# H-Bridge.net
KiCad netlist of a schematic drawn in Altium Designer
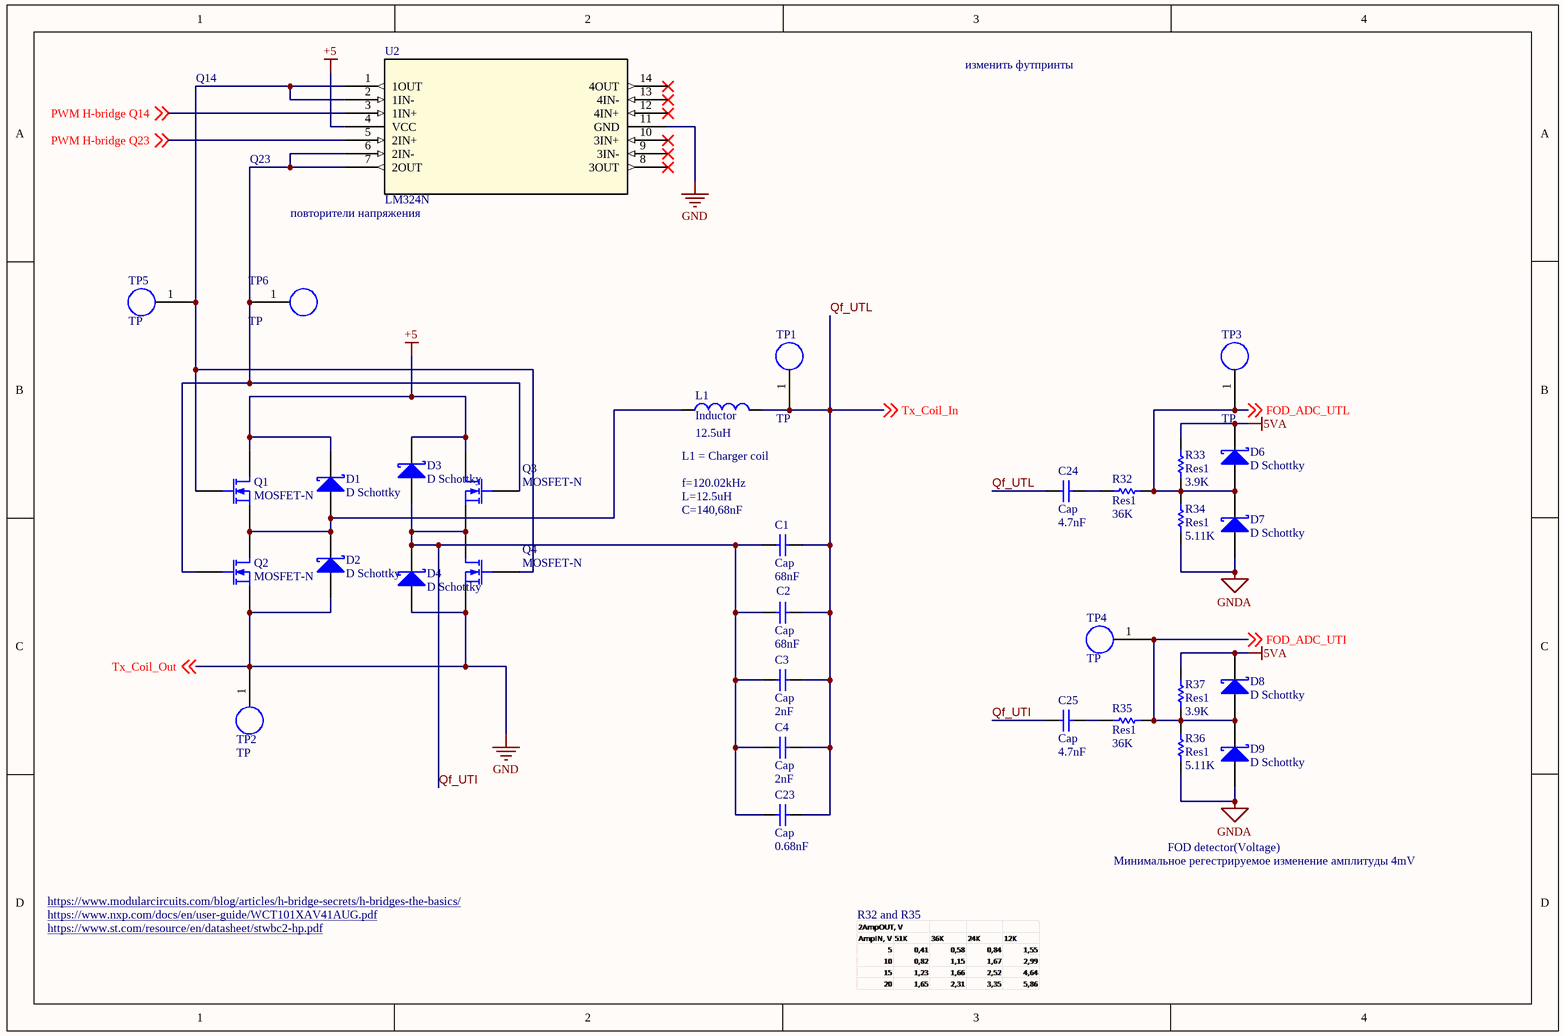
[diagram p0: H-Bridge.SchDoc]

(export (version "E")
  (design (tool "Eeschema 10.0.6"))
  (components
    (comp (ref "C1")
      (value "Cap")
      (footprint "CAP 0603_1608")
      (description "Capacitor")
      (fields (field (name "ALTIUM_VALUE") "68nF") (field (name "PUBLISHER") "Altium Limited"))
      (libsource (lib "Miscellaneous Devices") (part "Cap"))
    )
    (comp (ref "C2")
      (value "Cap")
      (footprint "CAP 0603_1608")
      (description "Capacitor")
      (fields (field (name "ALTIUM_VALUE") "68nF") (field (name "PUBLISHER") "Altium Limited"))
      (libsource (lib "Miscellaneous Devices") (part "Cap"))
    )
    (comp (ref "C3")
      (value "Cap")
      (footprint "CAP 0603_1608")
      (description "Capacitor")
      (fields (field (name "ALTIUM_VALUE") "2nF") (field (name "PUBLISHER") "Altium Limited"))
      (libsource (lib "Miscellaneous Devices") (part "Cap"))
    )
    (comp (ref "C4")
      (value "Cap")
      (footprint "CAP 0603_1608")
      (description "Capacitor")
      (fields (field (name "ALTIUM_VALUE") "2nF") (field (name "PUBLISHER") "Altium Limited"))
      (libsource (lib "Miscellaneous Devices") (part "Cap"))
    )
    (comp (ref "C23")
      (value "Cap")
      (footprint "CAP 0603_1608")
      (description "Capacitor")
      (fields (field (name "ALTIUM_VALUE") "0.68nF") (field (name "PUBLISHER") "Altium Limited"))
      (libsource (lib "Miscellaneous Devices") (part "Cap"))
    )
    (comp (ref "C24")
      (value "Cap")
      (footprint "CAP 0402_1005")
      (description "Capacitor")
      (fields (field (name "ALTIUM_VALUE") "4.7nF") (field (name "PUBLISHER") "Altium Limited"))
      (libsource (lib "Miscellaneous Devices") (part "Cap"))
    )
    (comp (ref "C25")
      (value "Cap")
      (footprint "CAP 0402_1005")
      (description "Capacitor")
      (fields (field (name "ALTIUM_VALUE") "4.7nF") (field (name "PUBLISHER") "Altium Limited"))
      (libsource (lib "Miscellaneous Devices") (part "Cap"))
    )
    (comp (ref "D1")
      (value "D Schottky")
      (footprint "SOD-123")
      (description "Schottky Diode")
      (fields (field (name "PUBLISHER") "Altium Limited"))
      (libsource (lib "Miscellaneous Devices") (part "D Schottky"))
    )
    (comp (ref "D2")
      (value "D Schottky")
      (footprint "SOD-123")
      (description "Schottky Diode")
      (fields (field (name "PUBLISHER") "Altium Limited"))
      (libsource (lib "Miscellaneous Devices") (part "D Schottky"))
    )
    (comp (ref "D3")
      (value "D Schottky")
      (footprint "SOD-123")
      (description "Schottky Diode")
      (fields (field (name "PUBLISHER") "Altium Limited"))
      (libsource (lib "Miscellaneous Devices") (part "D Schottky"))
    )
    (comp (ref "D4")
      (value "D Schottky")
      (footprint "SOD-123")
      (description "Schottky Diode")
      (fields (field (name "PUBLISHER") "Altium Limited"))
      (libsource (lib "Miscellaneous Devices") (part "D Schottky"))
    )
    (comp (ref "D6")
      (value "D Schottky")
      (footprint "SOD-123")
      (description "Schottky Diode")
      (fields (field (name "PUBLISHER") "Altium Limited"))
      (libsource (lib "Miscellaneous Devices") (part "D Schottky"))
    )
    (comp (ref "D7")
      (value "D Schottky")
      (footprint "SOD-123")
      (description "Schottky Diode")
      (fields (field (name "PUBLISHER") "Altium Limited"))
      (libsource (lib "Miscellaneous Devices") (part "D Schottky"))
    )
    (comp (ref "D8")
      (value "D Schottky")
      (footprint "SOD-123")
      (description "Schottky Diode")
      (fields (field (name "PUBLISHER") "Altium Limited"))
      (libsource (lib "Miscellaneous Devices") (part "D Schottky"))
    )
    (comp (ref "D9")
      (value "D Schottky")
      (footprint "SOD-123")
      (description "Schottky Diode")
      (fields (field (name "PUBLISHER") "Altium Limited"))
      (libsource (lib "Miscellaneous Devices") (part "D Schottky"))
    )
    (comp (ref "L1")
      (value "Inductor")
      (footprint "Charger_Coil1")
      (fields (field (name "ALTIUM_VALUE") "12.5uH") (field (name "PUBLISHER") "Altium Limited"))
      (libsource (lib "Miscellaneous Devices") (part "Inductor"))
    )
    (comp (ref "Q1")
      (value "MOSFET-N")
      (footprint "DIODES SOT-23-3")
      (description "N-Channel MOSFET")
      (fields (field (name "PUBLISHER") "Altium Limited"))
      (libsource (lib "Miscellaneous Devices") (part "MOSFET-N"))
    )
    (comp (ref "Q2")
      (value "MOSFET-N")
      (footprint "DIODES SOT-23-3")
      (description "N-Channel MOSFET")
      (fields (field (name "PUBLISHER") "Altium Limited"))
      (libsource (lib "Miscellaneous Devices") (part "MOSFET-N"))
    )
    (comp (ref "Q3")
      (value "MOSFET-N")
      (footprint "DIODES SOT-23-3")
      (description "N-Channel MOSFET")
      (fields (field (name "PUBLISHER") "Altium Limited"))
      (libsource (lib "Miscellaneous Devices") (part "MOSFET-N"))
    )
    (comp (ref "Q4")
      (value "MOSFET-N")
      (footprint "DIODES SOT-23-3")
      (description "N-Channel MOSFET")
      (fields (field (name "PUBLISHER") "Altium Limited"))
      (libsource (lib "Miscellaneous Devices") (part "MOSFET-N"))
    )
    (comp (ref "R32")
      (value "Res1")
      (footprint "RES 0402_1005")
      (description "Resistor")
      (fields (field (name "ALTIUM_VALUE") "36K") (field (name "PUBLISHER") "Altium Limited"))
      (libsource (lib "Miscellaneous Devices") (part "Res1"))
    )
    (comp (ref "R33")
      (value "Res1")
      (footprint "RES 0402_1005")
      (description "Resistor")
      (fields (field (name "ALTIUM_VALUE") "3.9K") (field (name "PUBLISHER") "Altium Limited"))
      (libsource (lib "Miscellaneous Devices") (part "Res1"))
    )
    (comp (ref "R34")
      (value "Res1")
      (footprint "RES 0603_1608")
      (description "Resistor")
      (fields (field (name "ALTIUM_VALUE") "5.11K") (field (name "PUBLISHER") "Altium Limited"))
      (libsource (lib "Miscellaneous Devices") (part "Res1"))
    )
    (comp (ref "R35")
      (value "Res1")
      (footprint "RES 0402_1005")
      (description "Resistor")
      (fields (field (name "ALTIUM_VALUE") "36K") (field (name "PUBLISHER") "Altium Limited"))
      (libsource (lib "Miscellaneous Devices") (part "Res1"))
    )
    (comp (ref "R36")
      (value "Res1")
      (footprint "RES 0603_1608")
      (description "Resistor")
      (fields (field (name "ALTIUM_VALUE") "5.11K") (field (name "PUBLISHER") "Altium Limited"))
      (libsource (lib "Miscellaneous Devices") (part "Res1"))
    )
    (comp (ref "R37")
      (value "Res1")
      (footprint "RES 0402_1005")
      (description "Resistor")
      (fields (field (name "ALTIUM_VALUE") "3.9K") (field (name "PUBLISHER") "Altium Limited"))
      (libsource (lib "Miscellaneous Devices") (part "Res1"))
    )
    (comp (ref "TP1")
      (value "TP")
      (footprint "Testpoint1")
      (libsource (lib "Testpoint1") (part "Testpoint1"))
    )
    (comp (ref "TP2")
      (value "TP")
      (footprint "Testpoint1")
      (libsource (lib "Testpoint1") (part "Testpoint1"))
    )
    (comp (ref "TP3")
      (value "TP")
      (footprint "Testpoint1")
      (libsource (lib "Testpoint1") (part "Testpoint1"))
    )
    (comp (ref "TP4")
      (value "TP")
      (footprint "Testpoint1")
      (libsource (lib "Testpoint1") (part "Testpoint1"))
    )
    (comp (ref "TP5")
      (value "TP")
      (footprint "Testpoint1")
      (libsource (lib "Testpoint1") (part "Testpoint1"))
    )
    (comp (ref "TP6")
      (value "TP")
      (footprint "Testpoint1")
      (libsource (lib "Testpoint1") (part "Testpoint1"))
    )
    (comp (ref "U2")
      (value "LM324N")
      (footprint "LM324NSR")
      (description "No Description Available")
      (libsource (lib "LM324N") (part "LM324N"))
    )
  )
  (nets
    (net (code "1") (name "+5") (class "Default")
      (node (ref "D1") (pin "2") (pinfunction "K_2") (pintype "passive"))
      (node (ref "D3") (pin "2") (pinfunction "K_2") (pintype "passive"))
      (node (ref "Q1") (pin "1") (pinfunction "D_1") (pintype "passive"))
      (node (ref "Q3") (pin "1") (pinfunction "D_1") (pintype "passive"))
      (node (ref "U2") (pin "4") (pinfunction "VCC_4") (pintype "power_in"))
    )
    (net (code "2") (name "/Qf_UTI") (class "Default")
      (node (ref "C1") (pin "1") (pinfunction "1_1") (pintype "passive"))
      (node (ref "C2") (pin "1") (pinfunction "1_1") (pintype "passive"))
      (node (ref "C23") (pin "2") (pinfunction "2_2") (pintype "passive"))
      (node (ref "C25") (pin "1") (pinfunction "1_1") (pintype "passive"))
      (node (ref "C3") (pin "1") (pinfunction "1_1") (pintype "passive"))
      (node (ref "C4") (pin "1") (pinfunction "1_1") (pintype "passive"))
      (node (ref "D3") (pin "1") (pinfunction "A_1") (pintype "passive"))
      (node (ref "D4") (pin "2") (pinfunction "K_2") (pintype "passive"))
      (node (ref "Q3") (pin "3") (pinfunction "S_3") (pintype "passive"))
      (node (ref "Q4") (pin "1") (pinfunction "D_1") (pintype "passive"))
    )
    (net (code "3") (name "5VA") (class "Default")
      (node (ref "D6") (pin "2") (pinfunction "K_2") (pintype "passive"))
      (node (ref "D8") (pin "2") (pinfunction "K_2") (pintype "passive"))
      (node (ref "R33") (pin "1") (pinfunction "1_1") (pintype "passive"))
      (node (ref "R37") (pin "2") (pinfunction "2_2") (pintype "passive"))
    )
    (net (code "4") (name "FOD_ADC_UTI") (class "Default")
      (node (ref "D8") (pin "1") (pinfunction "A_1") (pintype "passive"))
      (node (ref "D9") (pin "2") (pinfunction "K_2") (pintype "passive"))
      (node (ref "R35") (pin "2") (pinfunction "2_2") (pintype "passive"))
      (node (ref "R36") (pin "2") (pinfunction "2_2") (pintype "passive"))
      (node (ref "R37") (pin "1") (pinfunction "1_1") (pintype "passive"))
      (node (ref "TP4") (pin "1") (pintype "passive"))
    )
    (net (code "5") (name "FOD_ADC_UTL") (class "Default")
      (node (ref "D6") (pin "1") (pinfunction "A_1") (pintype "passive"))
      (node (ref "D7") (pin "2") (pinfunction "K_2") (pintype "passive"))
      (node (ref "R32") (pin "1") (pinfunction "1_1") (pintype "passive"))
      (node (ref "R33") (pin "2") (pinfunction "2_2") (pintype "passive"))
      (node (ref "R34") (pin "2") (pinfunction "2_2") (pintype "passive"))
      (node (ref "TP3") (pin "1") (pintype "passive"))
    )
    (net (code "6") (name "GND") (class "Default")
      (node (ref "D2") (pin "1") (pinfunction "A_1") (pintype "passive"))
      (node (ref "D4") (pin "1") (pinfunction "A_1") (pintype "passive"))
      (node (ref "Q2") (pin "3") (pinfunction "S_3") (pintype "passive"))
      (node (ref "Q4") (pin "3") (pinfunction "S_3") (pintype "passive"))
      (node (ref "TP2") (pin "1") (pintype "passive"))
      (node (ref "U2") (pin "11") (pinfunction "GND_11") (pintype "power_in"))
    )
    (net (code "7") (name "GNDA") (class "Default")
      (node (ref "D7") (pin "1") (pinfunction "A_1") (pintype "passive"))
      (node (ref "D9") (pin "1") (pinfunction "A_1") (pintype "passive"))
      (node (ref "R34") (pin "1") (pinfunction "1_1") (pintype "passive"))
      (node (ref "R36") (pin "1") (pinfunction "1_1") (pintype "passive"))
    )
    (net (code "8") (name "Net-(C24-Pad2)") (class "Default")
      (node (ref "C24") (pin "2") (pinfunction "2_2") (pintype "passive"))
      (node (ref "R32") (pin "2") (pinfunction "2_2") (pintype "passive"))
    )
    (net (code "9") (name "Net-(C25-Pad2)") (class "Default")
      (node (ref "C25") (pin "2") (pinfunction "2_2") (pintype "passive"))
      (node (ref "R35") (pin "1") (pinfunction "1_1") (pintype "passive"))
    )
    (net (code "10") (name "Net-(D1-A)") (class "Default")
      (node (ref "D1") (pin "1") (pinfunction "A_1") (pintype "passive"))
      (node (ref "D2") (pin "2") (pinfunction "K_2") (pintype "passive"))
      (node (ref "L1") (pin "1") (pinfunction "1_1") (pintype "passive"))
      (node (ref "Q1") (pin "3") (pinfunction "S_3") (pintype "passive"))
      (node (ref "Q2") (pin "1") (pinfunction "D_1") (pintype "passive"))
    )
    (net (code "11") (name "Net-(Q1-G)") (class "Default")
      (node (ref "Q1") (pin "2") (pinfunction "G_2") (pintype "passive"))
      (node (ref "Q4") (pin "2") (pinfunction "G_2") (pintype "passive"))
      (node (ref "TP5") (pin "1") (pintype "passive"))
      (node (ref "U2") (pin "1") (pinfunction "1OUT_1") (pintype "output"))
      (node (ref "U2") (pin "2") (pinfunction "1IN-_2") (pintype "input"))
    )
    (net (code "12") (name "Net-(Q2-G)") (class "Default")
      (node (ref "Q2") (pin "2") (pinfunction "G_2") (pintype "passive"))
      (node (ref "Q3") (pin "2") (pinfunction "G_2") (pintype "passive"))
      (node (ref "TP6") (pin "1") (pintype "passive"))
      (node (ref "U2") (pin "6") (pinfunction "2IN-_6") (pintype "input"))
      (node (ref "U2") (pin "7") (pinfunction "2OUT_7") (pintype "output"))
    )
    (net (code "13") (name "PWM H-bridge Q14") (class "Default")
      (node (ref "U2") (pin "3") (pinfunction "1IN+_3") (pintype "input"))
    )
    (net (code "14") (name "PWM H-bridge Q23") (class "Default")
      (node (ref "U2") (pin "5") (pinfunction "2IN+_5") (pintype "input"))
    )
    (net (code "15") (name "Tx_Coil_In") (class "Default")
      (node (ref "C1") (pin "2") (pinfunction "2_2") (pintype "passive"))
      (node (ref "C2") (pin "2") (pinfunction "2_2") (pintype "passive"))
      (node (ref "C23") (pin "1") (pinfunction "1_1") (pintype "passive"))
      (node (ref "C24") (pin "1") (pinfunction "1_1") (pintype "passive"))
      (node (ref "C3") (pin "2") (pinfunction "2_2") (pintype "passive"))
      (node (ref "C4") (pin "2") (pinfunction "2_2") (pintype "passive"))
      (node (ref "L1") (pin "2") (pinfunction "2_2") (pintype "passive"))
      (node (ref "TP1") (pin "1") (pintype "passive"))
    )
    (net (code "16") (name "unconnected-(U2-3IN+-Pad10)") (class "Default")
      (node (ref "U2") (pin "10") (pinfunction "3IN+_10") (pintype "input+no_connect"))
    )
    (net (code "17") (name "unconnected-(U2-3IN--Pad9)") (class "Default")
      (node (ref "U2") (pin "9") (pinfunction "3IN-_9") (pintype "input+no_connect"))
    )
    (net (code "18") (name "unconnected-(U2-3OUT-Pad8)") (class "Default")
      (node (ref "U2") (pin "8") (pinfunction "3OUT_8") (pintype "output+no_connect"))
    )
    (net (code "19") (name "unconnected-(U2-4IN+-Pad12)") (class "Default")
      (node (ref "U2") (pin "12") (pinfunction "4IN+_12") (pintype "input+no_connect"))
    )
    (net (code "20") (name "unconnected-(U2-4IN--Pad13)") (class "Default")
      (node (ref "U2") (pin "13") (pinfunction "4IN-_13") (pintype "input+no_connect"))
    )
    (net (code "21") (name "unconnected-(U2-4OUT-Pad14)") (class "Default")
      (node (ref "U2") (pin "14") (pinfunction "4OUT_14") (pintype "output+no_connect"))
    )
  )
)
